# schematic_sheet1.net
KiCad netlist of a schematic drawn in Altium Designer
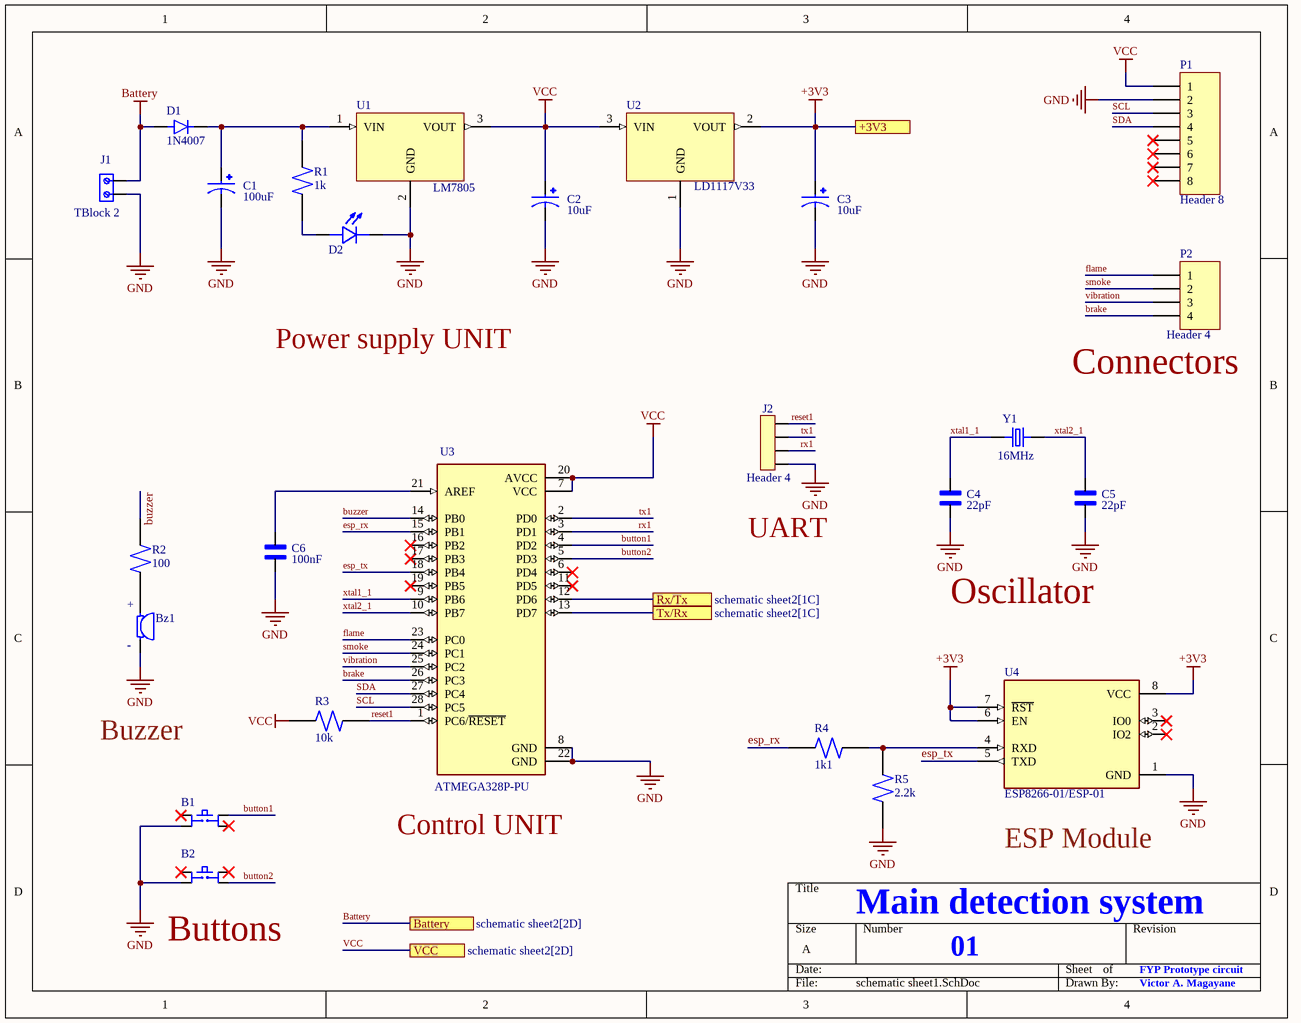
[diagram p0: schematic sheet1.SchDoc]

(export (version "E")
  (design (tool "Eeschema 10.0.6"))
  (components
    (comp (ref "B1")
      (value "Push button")
      (footprint "SW_TS02-66-95-BK-260-LCR-D")
      (libsource (lib "Installed library") (part "Push button"))
    )
    (comp (ref "B2")
      (value "Push button")
      (footprint "SW_TS02-66-95-BK-260-LCR-D")
      (libsource (lib "Installed library") (part "Push button"))
    )
    (comp (ref "Bz1")
      (value "AI-1223-TWT-12V-R")
      (footprint "XDCR_AI-1223-TWT-12V-R")
      (description "ELECTRO-MECHANICAL AUDIO INDICATOR")
      (fields (field (name "MF") "PUI Audio,"))
      (libsource (lib "Installed library") (part "Buzzer"))
    )
    (comp (ref "C1")
      (value "100uF")
      (footprint "CAPPRD500W50D500H1100")
      (description "FS-A")
      (fields (field (name "MF") "{'manufacturer': u'Panasonic'}") (field (name "MP") "EEUFS0J221B"))
      (libsource (lib "Installed library") (part "Electrolytic capacitor"))
    )
    (comp (ref "C2")
      (value "10uF")
      (footprint "CAPPRD500W50D500H1100")
      (description "FS-A")
      (fields (field (name "MF") "{'manufacturer': u'Panasonic'}") (field (name "MP") "EEUFS0J221B"))
      (libsource (lib "Installed library") (part "Electrolytic capacitor"))
    )
    (comp (ref "C3")
      (value "10uF")
      (footprint "CAPPRD500W50D500H1100")
      (description "FS-A")
      (fields (field (name "MF") "{'manufacturer': u'Panasonic'}") (field (name "MP") "EEUFS0J221B"))
      (libsource (lib "Installed library") (part "Electrolytic capacitor"))
    )
    (comp (ref "C4")
      (value "22pF")
      (footprint "CAPRB500W50L450T300H550")
      (description "2200 pF Â±10% 250V Ceramic Capacitor X7R Radial")
      (fields (field (name "DIGI-KEY_PART_NUMBER") "445-173386-1-ND") (field (name "MF") "TDK"))
      (libsource (lib "Installed library") (part "Ceramic capacitor"))
    )
    (comp (ref "C5")
      (value "22pF")
      (footprint "CAPRB500W50L450T300H550")
      (description "2200 pF Â±10% 250V Ceramic Capacitor X7R Radial")
      (fields (field (name "DIGI-KEY_PART_NUMBER") "445-173386-1-ND") (field (name "MF") "TDK"))
      (libsource (lib "Installed library") (part "Ceramic capacitor"))
    )
    (comp (ref "C6")
      (value "100nF")
      (footprint "CAPRB500W50L450T300H550")
      (description "2200 pF Â±10% 250V Ceramic Capacitor X7R Radial")
      (fields (field (name "DIGI-KEY_PART_NUMBER") "445-173386-1-ND") (field (name "MF") "TDK"))
      (libsource (lib "Installed library") (part "Ceramic capacitor"))
    )
    (comp (ref "D1")
      (value "1N4007")
      (footprint "DIOAD1060W80L520D270")
      (description "Diode Switching 1KV 1A 2-Pin DO-41")
      (libsource (lib "Components") (part "1N4007"))
    )
    (comp (ref "D2")
      (value "L08R5000Q1")
      (footprint "LEDRD254W57D500H1070")
      (description "LED, Orange, Through Hole, T-1 3/4 (5mm), 30 mA, 2.1 V, 635 nm")
      (fields (field (name "MF") "{'manufacturer': u'LED Technology'}"))
      (libsource (lib "Installed library") (part "LED"))
    )
    (comp (ref "J1")
      (value "TBlock 2")
      (footprint "691111710002")
      (description "2 Position Wire to Board Terminal Block Horizontal with Board 0.197 _5.00mm_ Through Hole")
      (fields (field (name "MP") "691111710002") (field (name "MF") "Wurth Electronics"))
      (libsource (lib "Installed library") (part "Terminal Block - 2Pins"))
    )
    (comp (ref "J2")
      (value "Header 4")
      (footprint "SULLINS_PPTC041LFBN-RC")
      (description "4 Position Header Connector Through Hole")
      (fields (field (name "MP") "PPTC041LFBN-RC") (field (name "MF") "Sullins Connector"))
      (libsource (lib "Installed library") (part "Female header - 4Pins"))
    )
    (comp (ref "P1")
      (value "Header 8")
      (footprint "HDR1X8")
      (description "Header, 8-Pin")
      (fields (field (name "PUBLISHER") "Altium Limited"))
      (libsource (lib "Miscellaneous Connectors") (part "Header 8"))
    )
    (comp (ref "P2")
      (value "Header 4")
      (footprint "HDR1X4")
      (description "Header, 4-Pin")
      (fields (field (name "PUBLISHER") "Altium Limited"))
      (libsource (lib "Miscellaneous Connectors") (part "Header 4"))
    )
    (comp (ref "R1")
      (value "1k")
      (footprint "RESAD1100W55L680D260")
      (description "(MFR-25FBF52-10K) 10,2 kOhm bei 1% 0,25W, 1/4W Durchbohrlochwiderstand Axial Metal Film")
      (fields (field (name "DIGI-KEY_PART_NUMBER") "10.2KXBK-ND") (field (name "MF") "Yageo"))
      (libsource (lib "Installed library") (part "Resistor (0.25W)"))
    )
    (comp (ref "R2")
      (value "100")
      (footprint "RESAD1100W55L680D260")
      (description "(MFR-25FBF52-10K) 10,2 kOhm bei 1% 0,25W, 1/4W Durchbohrlochwiderstand Axial Metal Film")
      (fields (field (name "DIGI-KEY_PART_NUMBER") "10.2KXBK-ND") (field (name "MF") "Yageo"))
      (libsource (lib "Installed library") (part "Resistor (0.25W)"))
    )
    (comp (ref "R3")
      (value "10k")
      (footprint "RESAD1100W55L680D260")
      (description "(MFR-25FBF52-10K) 10,2 kOhm bei 1% 0,25W, 1/4W Durchbohrlochwiderstand Axial Metal Film")
      (fields (field (name "DIGI-KEY_PART_NUMBER") "10.2KXBK-ND") (field (name "MF") "Yageo"))
      (libsource (lib "Installed library") (part "Resistor (0.25W)"))
    )
    (comp (ref "R4")
      (value "1k1")
      (footprint "RESAD1100W55L680D260")
      (description "(MFR-25FBF52-10K) 10,2 kOhm bei 1% 0,25W, 1/4W Durchbohrlochwiderstand Axial Metal Film")
      (fields (field (name "DIGI-KEY_PART_NUMBER") "10.2KXBK-ND") (field (name "MF") "Yageo"))
      (libsource (lib "Installed library") (part "Resistor (0.25W)"))
    )
    (comp (ref "R5")
      (value "2.2k")
      (footprint "RESAD1100W55L680D260")
      (description "(MFR-25FBF52-10K) 10,2 kOhm bei 1% 0,25W, 1/4W Durchbohrlochwiderstand Axial Metal Film")
      (fields (field (name "DIGI-KEY_PART_NUMBER") "10.2KXBK-ND") (field (name "MF") "Yageo"))
      (libsource (lib "Installed library") (part "Resistor (0.25W)"))
    )
    (comp (ref "U1")
      (value "LM7805")
      (footprint "TO255P1020X450X1968-3")
      (fields (field (name "MP") "LM7805CT/NOPB"))
      (libsource (lib "Voltage regulator") (part "LM78__"))
    )
    (comp (ref "U2")
      (value "LD1117V33")
      (footprint "TO255P1020X450X1968-3")
      (libsource (lib "Voltage regulator") (part "LD1117V33"))
    )
    (comp (ref "U3")
      (value "ATMEGA328P-PU")
      (footprint "DIP794W46P254L2967H457Q28B")
      (description "ATmega Series 20 MHz 32 KB Flash 2 KB SRAM 8-Bit Microcontroller - DIP-28")
      (libsource (lib "Installed library") (part "ATMEGA328P-PU"))
    )
    (comp (ref "U4")
      (value "ESP8266-01/ESP-01")
      (footprint "XCVR_ESP8266-01/ESP-01")
      (libsource (lib "Installed library") (part "ESP8266-01 Module"))
    )
    (comp (ref "Y1")
      (value "16MHz")
      (footprint "XTAL_ECS-160-20-4X")
      (description "CRYSTAL T/H")
      (fields (field (name "MF") "{'manufacturer': u'ECS Inc.'}") (field (name "MP") "ECS-160-S-4"))
      (libsource (lib "Installed library") (part "Crystal oscilator"))
    )
  )
  (nets
    (net (code "1") (name "+3V3") (class "Default")
      (node (ref "C3") (pin "P") (pinfunction "P_P") (pintype "passive"))
      (node (ref "U2") (pin "2") (pinfunction "VOUT_2") (pintype "output"))
      (node (ref "U4") (pin "6") (pinfunction "EN_6") (pintype "input"))
      (node (ref "U4") (pin "7") (pinfunction "~{RST}_7") (pintype "input"))
      (node (ref "U4") (pin "8") (pinfunction "VCC_8") (pintype "power_in"))
    )
    (net (code "2") (name "/Rx{slash}Tx") (class "Default")
      (node (ref "U3") (pin "12") (pinfunction "PD6_12") (pintype "bidirectional"))
    )
    (net (code "3") (name "/SCL") (class "Default")
      (node (ref "P1") (pin "3") (pinfunction "3_3") (pintype "passive"))
      (node (ref "U3") (pin "28") (pinfunction "PC5_28") (pintype "bidirectional"))
    )
    (net (code "4") (name "/SDA") (class "Default")
      (node (ref "P1") (pin "4") (pinfunction "4_4") (pintype "passive"))
      (node (ref "U3") (pin "27") (pinfunction "PC4_27") (pintype "bidirectional"))
    )
    (net (code "5") (name "/Tx{slash}Rx") (class "Default")
      (node (ref "U3") (pin "13") (pinfunction "PD7_13") (pintype "bidirectional"))
    )
    (net (code "6") (name "/brake") (class "Default")
      (node (ref "P2") (pin "4") (pinfunction "4_4") (pintype "passive"))
      (node (ref "U3") (pin "26") (pinfunction "PC3_26") (pintype "bidirectional"))
    )
    (net (code "7") (name "/button1") (class "Default")
      (node (ref "B1") (pin "3") (pinfunction "3_3") (pintype "passive"))
      (node (ref "U3") (pin "4") (pinfunction "PD2_4") (pintype "bidirectional"))
    )
    (net (code "8") (name "/button2") (class "Default")
      (node (ref "B2") (pin "4") (pinfunction "4_4") (pintype "passive"))
      (node (ref "U3") (pin "5") (pinfunction "PD3_5") (pintype "bidirectional"))
    )
    (net (code "9") (name "/buzzer") (class "Default")
      (node (ref "R2") (pin "2") (pinfunction "2_2") (pintype "passive"))
      (node (ref "U3") (pin "14") (pinfunction "PB0_14") (pintype "bidirectional"))
    )
    (net (code "10") (name "/esp_rx") (class "Default")
      (node (ref "R4") (pin "2") (pinfunction "2_2") (pintype "passive"))
      (node (ref "U3") (pin "15") (pinfunction "PB1_15") (pintype "bidirectional"))
    )
    (net (code "11") (name "/esp_tx") (class "Default")
      (node (ref "U3") (pin "18") (pinfunction "PB4_18") (pintype "bidirectional"))
      (node (ref "U4") (pin "5") (pinfunction "TXD_5") (pintype "output"))
    )
    (net (code "12") (name "/flame") (class "Default")
      (node (ref "P2") (pin "1") (pinfunction "1_1") (pintype "passive"))
      (node (ref "U3") (pin "23") (pinfunction "PC0_23") (pintype "bidirectional"))
    )
    (net (code "13") (name "/reset1") (class "Default")
      (node (ref "J2") (pin "1") (pinfunction "1_1") (pintype "passive"))
      (node (ref "R3") (pin "2") (pinfunction "2_2") (pintype "passive"))
      (node (ref "U3") (pin "1") (pinfunction "PC6/~{RESET}_1") (pintype "bidirectional"))
    )
    (net (code "14") (name "/rx1") (class "Default")
      (node (ref "J2") (pin "3") (pinfunction "3_3") (pintype "passive"))
      (node (ref "U3") (pin "3") (pinfunction "PD1_3") (pintype "bidirectional"))
    )
    (net (code "15") (name "/smoke") (class "Default")
      (node (ref "P2") (pin "2") (pinfunction "2_2") (pintype "passive"))
      (node (ref "U3") (pin "24") (pinfunction "PC1_24") (pintype "bidirectional"))
    )
    (net (code "16") (name "/tx1") (class "Default")
      (node (ref "J2") (pin "2") (pinfunction "2_2") (pintype "passive"))
      (node (ref "U3") (pin "2") (pinfunction "PD0_2") (pintype "bidirectional"))
    )
    (net (code "17") (name "/vibration") (class "Default")
      (node (ref "P2") (pin "3") (pinfunction "3_3") (pintype "passive"))
      (node (ref "U3") (pin "25") (pinfunction "PC2_25") (pintype "bidirectional"))
    )
    (net (code "18") (name "/xtal1_1") (class "Default")
      (node (ref "C4") (pin "1") (pinfunction "1_1") (pintype "passive"))
      (node (ref "U3") (pin "9") (pinfunction "PB6_9") (pintype "bidirectional"))
      (node (ref "Y1") (pin "1") (pinfunction "1_1") (pintype "passive"))
    )
    (net (code "19") (name "/xtal2_1") (class "Default")
      (node (ref "C5") (pin "1") (pinfunction "1_1") (pintype "passive"))
      (node (ref "U3") (pin "10") (pinfunction "PB7_10") (pintype "bidirectional"))
      (node (ref "Y1") (pin "2") (pinfunction "2_2") (pintype "passive"))
    )
    (net (code "20") (name "Battery") (class "Default")
      (node (ref "D1") (pin "A") (pinfunction "A_A") (pintype "passive"))
      (node (ref "J1") (pin "2") (pinfunction "2_2") (pintype "passive"))
    )
    (net (code "21") (name "GND") (class "Default")
      (node (ref "B1") (pin "2") (pinfunction "2_2") (pintype "passive"))
      (node (ref "B2") (pin "2") (pinfunction "2_2") (pintype "passive"))
      (node (ref "Bz1") (pin "N") (pinfunction "NEG_N") (pintype "passive"))
      (node (ref "C1") (pin "N") (pinfunction "N_N") (pintype "passive"))
      (node (ref "C2") (pin "N") (pinfunction "N_N") (pintype "passive"))
      (node (ref "C3") (pin "N") (pinfunction "N_N") (pintype "passive"))
      (node (ref "C4") (pin "2") (pinfunction "2_2") (pintype "passive"))
      (node (ref "C5") (pin "2") (pinfunction "2_2") (pintype "passive"))
      (node (ref "C6") (pin "2") (pinfunction "2_2") (pintype "passive"))
      (node (ref "D2") (pin "C") (pinfunction "C_C") (pintype "passive"))
      (node (ref "J1") (pin "1") (pinfunction "1_1") (pintype "passive"))
      (node (ref "J2") (pin "4") (pinfunction "4_4") (pintype "passive"))
      (node (ref "P1") (pin "2") (pinfunction "2_2") (pintype "passive"))
      (node (ref "R5") (pin "1") (pinfunction "1_1") (pintype "passive"))
      (node (ref "U1") (pin "2") (pinfunction "GND_2") (pintype "passive"))
      (node (ref "U2") (pin "1") (pinfunction "GND_1") (pintype "passive"))
      (node (ref "U3") (pin "22") (pinfunction "GND_22") (pintype "power_in"))
      (node (ref "U3") (pin "8") (pinfunction "GND_8") (pintype "power_in"))
      (node (ref "U4") (pin "1") (pinfunction "GND_1") (pintype "power_in"))
    )
    (net (code "22") (name "Net-(Bz1-POS)") (class "Default")
      (node (ref "Bz1") (pin "P") (pinfunction "POS_P") (pintype "passive"))
      (node (ref "R2") (pin "1") (pinfunction "1_1") (pintype "passive"))
    )
    (net (code "23") (name "Net-(D2-PadA)") (class "Default")
      (node (ref "D2") (pin "A") (pinfunction "A_A") (pintype "passive"))
      (node (ref "R1") (pin "2") (pinfunction "2_2") (pintype "passive"))
    )
    (net (code "24") (name "Net-(U1-VIN)") (class "Default")
      (node (ref "C1") (pin "P") (pinfunction "P_P") (pintype "passive"))
      (node (ref "D1") (pin "C") (pinfunction "C_C") (pintype "passive"))
      (node (ref "R1") (pin "1") (pinfunction "1_1") (pintype "passive"))
      (node (ref "U1") (pin "1") (pinfunction "VIN_1") (pintype "input"))
    )
    (net (code "25") (name "Net-(U3-AREF)") (class "Default")
      (node (ref "C6") (pin "1") (pinfunction "1_1") (pintype "passive"))
      (node (ref "U3") (pin "21") (pinfunction "AREF_21") (pintype "input"))
    )
    (net (code "26") (name "Net-(U4-RXD)") (class "Default")
      (node (ref "R4") (pin "1") (pinfunction "1_1") (pintype "passive"))
      (node (ref "R5") (pin "2") (pinfunction "2_2") (pintype "passive"))
      (node (ref "U4") (pin "4") (pinfunction "RXD_4") (pintype "input"))
    )
    (net (code "27") (name "VCC") (class "Default")
      (node (ref "C2") (pin "P") (pinfunction "P_P") (pintype "passive"))
      (node (ref "P1") (pin "1") (pinfunction "1_1") (pintype "passive"))
      (node (ref "R3") (pin "1") (pinfunction "1_1") (pintype "passive"))
      (node (ref "U1") (pin "3") (pinfunction "VOUT_3") (pintype "output"))
      (node (ref "U2") (pin "3") (pinfunction "VIN_3") (pintype "input"))
      (node (ref "U3") (pin "20") (pinfunction "AVCC_20") (pintype "power_in"))
      (node (ref "U3") (pin "7") (pinfunction "VCC_7") (pintype "power_in"))
    )
    (net (code "28") (name "unconnected-(B1-Pad1)") (class "Default")
      (node (ref "B1") (pin "1") (pinfunction "1_1") (pintype "passive+no_connect"))
    )
    (net (code "29") (name "unconnected-(B1-Pad4)") (class "Default")
      (node (ref "B1") (pin "4") (pinfunction "4_4") (pintype "passive+no_connect"))
    )
    (net (code "30") (name "unconnected-(B2-Pad1)") (class "Default")
      (node (ref "B2") (pin "1") (pinfunction "1_1") (pintype "passive+no_connect"))
    )
    (net (code "31") (name "unconnected-(B2-Pad3)") (class "Default")
      (node (ref "B2") (pin "3") (pinfunction "3_3") (pintype "passive+no_connect"))
    )
    (net (code "32") (name "unconnected-(P1-Pad5)") (class "Default")
      (node (ref "P1") (pin "5") (pinfunction "5_5") (pintype "passive+no_connect"))
    )
    (net (code "33") (name "unconnected-(P1-Pad6)") (class "Default")
      (node (ref "P1") (pin "6") (pinfunction "6_6") (pintype "passive+no_connect"))
    )
    (net (code "34") (name "unconnected-(P1-Pad7)") (class "Default")
      (node (ref "P1") (pin "7") (pinfunction "7_7") (pintype "passive+no_connect"))
    )
    (net (code "35") (name "unconnected-(P1-Pad8)") (class "Default")
      (node (ref "P1") (pin "8") (pinfunction "8_8") (pintype "passive+no_connect"))
    )
    (net (code "36") (name "unconnected-(U3-PB2-Pad16)") (class "Default")
      (node (ref "U3") (pin "16") (pinfunction "PB2_16") (pintype "bidirectional+no_connect"))
    )
    (net (code "37") (name "unconnected-(U3-PB3-Pad17)") (class "Default")
      (node (ref "U3") (pin "17") (pinfunction "PB3_17") (pintype "bidirectional+no_connect"))
    )
    (net (code "38") (name "unconnected-(U3-PB5-Pad19)") (class "Default")
      (node (ref "U3") (pin "19") (pinfunction "PB5_19") (pintype "bidirectional+no_connect"))
    )
    (net (code "39") (name "unconnected-(U3-PD4-Pad6)") (class "Default")
      (node (ref "U3") (pin "6") (pinfunction "PD4_6") (pintype "bidirectional+no_connect"))
    )
    (net (code "40") (name "unconnected-(U3-PD5-Pad11)") (class "Default")
      (node (ref "U3") (pin "11") (pinfunction "PD5_11") (pintype "bidirectional+no_connect"))
    )
    (net (code "41") (name "unconnected-(U4-IO0-Pad3)") (class "Default")
      (node (ref "U4") (pin "3") (pinfunction "IO0_3") (pintype "bidirectional+no_connect"))
    )
    (net (code "42") (name "unconnected-(U4-IO2-Pad2)") (class "Default")
      (node (ref "U4") (pin "2") (pinfunction "IO2_2") (pintype "bidirectional+no_connect"))
    )
  )
)
